# PCB_AUTO-HANDWASH-THERMOMETER.net
KiCad netlist of a schematic drawn in Altium Designer
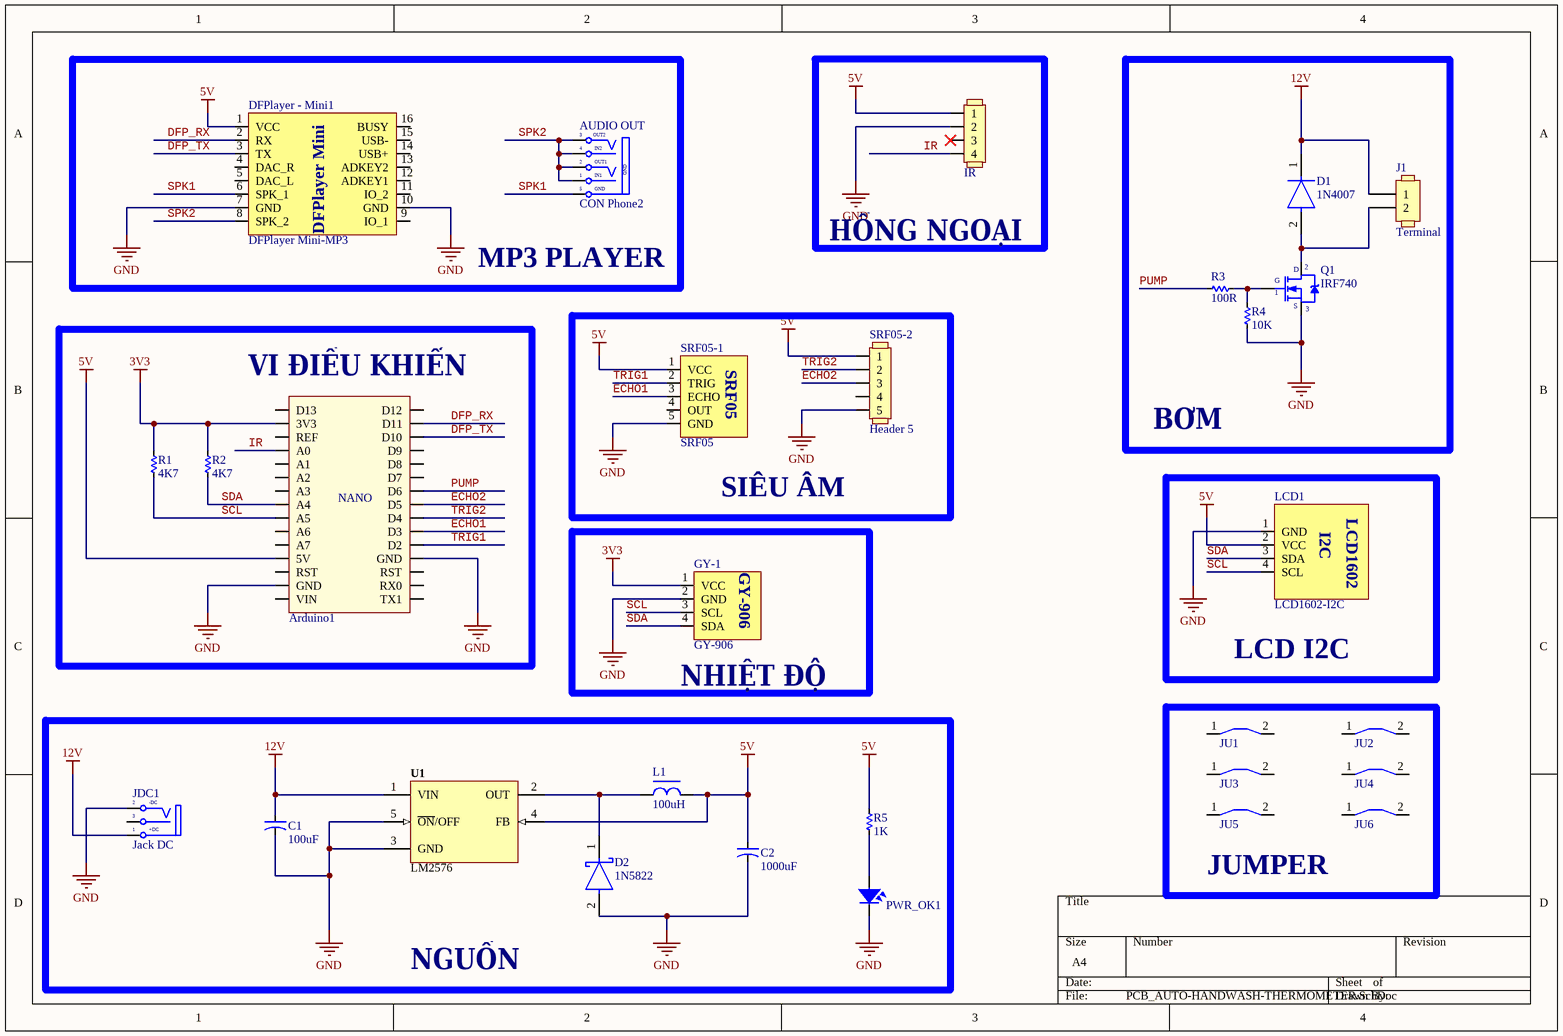
[diagram p0: PCB_AUTO-HANDWASH-THERMOMETER.SchDoc]

(export (version "E")
  (design (tool "Eeschema 10.0.6"))
  (components
    (comp (ref "Arduino1")
      (value "Arduino Nano")
      (footprint "Arduino Nano")
      (description "Arduino NANO")
      (libsource (lib "LIBRARY_MuaLinhKien") (part "Arduino Nano"))
    )
    (comp (ref "AUDIO OUT")
      (value "CON Phone2")
      (footprint "CON Phone2")
      (description "Jac Phone Stereo")
      (fields (field (name "CREAT BY") "VanDungEvn@Gmail.com"))
      (libsource (lib "LIBRARY_MuaLinhKien") (part "CON Phone2"))
    )
    (comp (ref "C1")
      (value "100uF")
      (footprint "CA-ALU-16")
      (description "Capacitor (Semiconductor SIM Model)")
      (fields (field (name "PUBLISHER") "Altium Limited"))
      (libsource (lib "LIBRARY_MuaLinhKien") (part "CN-ALU-DIP"))
    )
    (comp (ref "C2")
      (value "1000uF")
      (footprint "CA-ALU-16")
      (description "Capacitor (Semiconductor SIM Model)")
      (fields (field (name "PUBLISHER") "Altium Limited"))
      (libsource (lib "LIBRARY_MuaLinhKien") (part "CN-ALU-DIP"))
    )
    (comp (ref "D1")
      (value "1N4007")
      (footprint "FP-1N4007-MFG")
      (description "Rectifier diode 1000 V 1 A DO-41, ,")
      (fields
        (field (name "MANUFACTURER") "Diotec")
        (field (name "OCTOPART") "https://octopart.com/1n4007-diotec-4040411")
      )
      (libsource (lib "Altium Content Vault") (part "d7152d700b627762746794eb795d46e"))
    )
    (comp (ref "D2")
      (value "1N5822")
      (footprint "FP-DO-201AD-MFG")
      (description "DIODE SCHOTTKY 40V 3A DO201AD")
      (fields
        (field (name "OCTOPART") "https://octopart.com/1n5822-stmicroelectronics-323225")
        (field (name "MANUFACTURER") "STMicroelectronics")
      )
      (libsource (lib "Altium Content Vault") (part "1d6ec82d83fb6aee721767c19dac4b9"))
    )
    (comp (ref "DFPlayer - Mini1")
      (value "DFPlayer Mini-MP3")
      (footprint "DFPlayer Mini")
      (libsource (lib "tunaSchlib") (part "DFPlayer Mini-MP3"))
    )
    (comp (ref "GY-1") (value "GY-906") (footprint "GY-906") (libsource (lib "tunaSchlib") (part "GY-906")))
    (comp (ref "IR") (value "Header 4") (footprint "HEADER x4") (libsource (lib "Duc") (part "Header 4")))
    (comp (ref "J1")
      (value "Terminal")
      (footprint "Terminal x2 5mm")
      (description "Terminal x2")
      (libsource (lib "Duc") (part "Terminal x2"))
    )
    (comp (ref "JDC1")
      (value "Jack DC")
      (footprint "DC0")
      (description "Jac DC input")
      (libsource (lib "LIBRARY_MuaLinhKien") (part "DCIN"))
    )
    (comp (ref "JU1")
      (value "JUMPER")
      (footprint "JUMPER 15MM")
      (libsource (lib "tunaSchlib") (part "JUMPER"))
    )
    (comp (ref "JU2")
      (value "JUMPER")
      (footprint "JUMPER 10MM")
      (libsource (lib "tunaSchlib") (part "JUMPER"))
    )
    (comp (ref "JU3")
      (value "JUMPER")
      (footprint "JUMPER 5MM")
      (libsource (lib "tunaSchlib") (part "JUMPER"))
    )
    (comp (ref "JU4")
      (value "JUMPER")
      (footprint "JUMPER 5MM")
      (libsource (lib "tunaSchlib") (part "JUMPER"))
    )
    (comp (ref "JU5")
      (value "JUMPER")
      (footprint "JUMPER 5MM")
      (libsource (lib "tunaSchlib") (part "JUMPER"))
    )
    (comp (ref "JU6")
      (value "JUMPER")
      (footprint "JUMPER 5MM")
      (libsource (lib "tunaSchlib") (part "JUMPER"))
    )
    (comp (ref "L1")
      (value "100uH")
      (footprint "L-DIP-M-8")
      (description "Inductor")
      (libsource (lib "LIBRARY_MuaLinhKien") (part "L-DIP-1"))
    )
    (comp (ref "LCD1")
      (value "LCD1602-I2C")
      (footprint "LCD1602-I2C")
      (libsource (lib "tunaSchlib") (part "LCD1602-I2C"))
    )
    (comp (ref "PWR_OK1")
      (value "LED")
      (footprint "LED-5-RED")
      (description "LED Single colour Green and Red")
      (libsource (lib "LIBRARY_MuaLinhKien") (part "LED"))
    )
    (comp (ref "Q1")
      (value "IRF740")
      (footprint "TO220H1")
      (description "MOSFET N - CHANNEL 500V - 0.75 - 8A - TO-220")
      (libsource (lib "LIBRARY_MuaLinhKien") (part "IRF840"))
    )
    (comp (ref "R1")
      (value "4K7")
      (footprint "RES-1/4W")
      (description "Res")
      (fields
        (field (name "MANUFACTURER") "Generic Components")
        (field (name "PUBLISHER") "Altium Hobart Technology Centre")
      )
      (libsource (lib "LIBRARY_MuaLinhKien") (part "Res"))
    )
    (comp (ref "R2")
      (value "4K7")
      (footprint "RES-1/4W")
      (description "Res")
      (fields
        (field (name "MANUFACTURER") "Generic Components")
        (field (name "PUBLISHER") "Altium Hobart Technology Centre")
      )
      (libsource (lib "LIBRARY_MuaLinhKien") (part "Res"))
    )
    (comp (ref "R3")
      (value "100R")
      (footprint "RES-1/4W")
      (description "Res")
      (fields
        (field (name "MANUFACTURER") "Generic Components")
        (field (name "PUBLISHER") "Altium Hobart Technology Centre")
      )
      (libsource (lib "LIBRARY_MuaLinhKien") (part "Res"))
    )
    (comp (ref "R4")
      (value "10K")
      (footprint "RES-1/4W")
      (description "Res")
      (fields
        (field (name "MANUFACTURER") "Generic Components")
        (field (name "PUBLISHER") "Altium Hobart Technology Centre")
      )
      (libsource (lib "LIBRARY_MuaLinhKien") (part "Res"))
    )
    (comp (ref "R5")
      (value "1K")
      (footprint "RES-1/4W")
      (description "Res")
      (fields
        (field (name "MANUFACTURER") "Generic Components")
        (field (name "PUBLISHER") "Altium Hobart Technology Centre")
      )
      (libsource (lib "LIBRARY_MuaLinhKien") (part "Res"))
    )
    (comp (ref "SRF05-1") (value "SRF05") (footprint "SRF05") (libsource (lib "tunaSchlib") (part "SRF05")))
    (comp (ref "SRF05-2")
      (value "Header 5")
      (footprint "HEADER x5")
      (libsource (lib "Duc") (part "Header 5"))
    )
    (comp (ref "U1")
      (value "LM2576")
      (footprint "DIP5-T")
      (libsource (lib "LIBRARY_MuaLinhKien") (part "LM2576"))
    )
  )
  (nets
    (net (code "1") (name "/DFP_RX") (class "Default")
      (node (ref "Arduino1") (pin "D11") (pinfunction "D11_D11") (pintype "passive"))
      (node (ref "DFPlayer - Mini1") (pin "2") (pinfunction "RX_2") (pintype "power_in"))
    )
    (net (code "2") (name "/DFP_TX") (class "Default")
      (node (ref "Arduino1") (pin "D10") (pinfunction "D10_D10") (pintype "passive"))
      (node (ref "DFPlayer - Mini1") (pin "3") (pinfunction "TX_3") (pintype "power_in"))
    )
    (net (code "3") (name "/ECHO1") (class "Default")
      (node (ref "Arduino1") (pin "D3") (pinfunction "D3_D3") (pintype "passive"))
      (node (ref "SRF05-1") (pin "3") (pinfunction "ECHO_3") (pintype "power_in"))
    )
    (net (code "4") (name "/ECHO2") (class "Default")
      (node (ref "Arduino1") (pin "D5") (pinfunction "D5_D5") (pintype "passive"))
      (node (ref "SRF05-2") (pin "3") (pinfunction "3_3") (pintype "passive"))
    )
    (net (code "5") (name "/IR") (class "Default")
      (node (ref "Arduino1") (pin "A0") (pinfunction "A0_A0") (pintype "passive"))
      (node (ref "IR") (pin "4") (pinfunction "4_4") (pintype "passive"))
    )
    (net (code "6") (name "/PUMP") (class "Default")
      (node (ref "Arduino1") (pin "D6") (pinfunction "D6_D6") (pintype "passive"))
      (node (ref "R3") (pin "2") (pinfunction "2_2") (pintype "passive"))
    )
    (net (code "7") (name "/SCL") (class "Default")
      (node (ref "Arduino1") (pin "A5") (pinfunction "A5_A5") (pintype "passive"))
      (node (ref "GY-1") (pin "3") (pinfunction "SCL_3") (pintype "power_in"))
      (node (ref "LCD1") (pin "4") (pinfunction "SCL_4") (pintype "power_in"))
      (node (ref "R1") (pin "2") (pinfunction "2_2") (pintype "passive"))
    )
    (net (code "8") (name "/SDA") (class "Default")
      (node (ref "Arduino1") (pin "A4") (pinfunction "A4_A4") (pintype "passive"))
      (node (ref "GY-1") (pin "4") (pinfunction "SDA_4") (pintype "power_in"))
      (node (ref "LCD1") (pin "3") (pinfunction "SDA_3") (pintype "power_in"))
      (node (ref "R2") (pin "2") (pinfunction "2_2") (pintype "passive"))
    )
    (net (code "9") (name "/SPK1") (class "Default")
      (node (ref "AUDIO OUT") (pin "5") (pinfunction "GND_5") (pintype "passive"))
      (node (ref "DFPlayer - Mini1") (pin "6") (pinfunction "SPK_1_6") (pintype "power_in"))
    )
    (net (code "10") (name "/SPK2") (class "Default")
      (node (ref "AUDIO OUT") (pin "1") (pinfunction "S1_1") (pintype "power_in"))
      (node (ref "AUDIO OUT") (pin "2") (pinfunction "S1_2") (pintype "passive"))
      (node (ref "AUDIO OUT") (pin "3") (pinfunction "TN_3") (pintype "passive"))
      (node (ref "AUDIO OUT") (pin "4") (pinfunction "S_4") (pintype "power_in"))
      (node (ref "DFPlayer - Mini1") (pin "8") (pinfunction "SPK_2_8") (pintype "power_in"))
    )
    (net (code "11") (name "/TRIG1") (class "Default")
      (node (ref "Arduino1") (pin "D2") (pinfunction "D2_D2") (pintype "passive"))
      (node (ref "SRF05-1") (pin "2") (pinfunction "TRIG_2") (pintype "power_in"))
    )
    (net (code "12") (name "/TRIG2") (class "Default")
      (node (ref "Arduino1") (pin "D4") (pinfunction "D4_D4") (pintype "passive"))
      (node (ref "SRF05-2") (pin "2") (pinfunction "2_2") (pintype "passive"))
    )
    (net (code "13") (name "3V3") (class "Default")
      (node (ref "Arduino1") (pin "3V3") (pinfunction "3V3_3V3") (pintype "passive"))
      (node (ref "GY-1") (pin "1") (pinfunction "VCC_1") (pintype "power_in"))
      (node (ref "R1") (pin "1") (pinfunction "1_1") (pintype "passive"))
      (node (ref "R2") (pin "1") (pinfunction "1_1") (pintype "passive"))
    )
    (net (code "14") (name "5V") (class "Default")
      (node (ref "Arduino1") (pin "5V") (pinfunction "5V_5V") (pintype "passive"))
      (node (ref "C2") (pin "1") (pinfunction "1_1") (pintype "passive"))
      (node (ref "DFPlayer - Mini1") (pin "1") (pinfunction "VCC_1") (pintype "power_in"))
      (node (ref "IR") (pin "1") (pinfunction "1_1") (pintype "passive"))
      (node (ref "L1") (pin "2") (pinfunction "2_2") (pintype "passive"))
      (node (ref "LCD1") (pin "2") (pinfunction "VCC_2") (pintype "power_in"))
      (node (ref "R5") (pin "1") (pinfunction "1_1") (pintype "passive"))
      (node (ref "SRF05-1") (pin "1") (pinfunction "VCC_1") (pintype "power_in"))
      (node (ref "SRF05-2") (pin "1") (pinfunction "1_1") (pintype "passive"))
      (node (ref "U1") (pin "4") (pinfunction "FB_4") (pintype "input"))
    )
    (net (code "15") (name "12V") (class "Default")
      (node (ref "C1") (pin "1") (pinfunction "1_1") (pintype "passive"))
      (node (ref "D1") (pin "1") (pinfunction "C_1") (pintype "passive"))
      (node (ref "J1") (pin "1") (pinfunction "1_1") (pintype "passive"))
      (node (ref "JDC1") (pin "1") (pinfunction "T_1") (pintype "passive"))
      (node (ref "U1") (pin "1") (pinfunction "VIN_1") (pintype "power_in"))
    )
    (net (code "16") (name "GND") (class "Default")
      (node (ref "Arduino1") (pin "GND") (pinfunction "GND_GND") (pintype "passive"))
      (node (ref "C1") (pin "2") (pinfunction "2_2") (pintype "passive"))
      (node (ref "C2") (pin "2") (pinfunction "2_2") (pintype "passive"))
      (node (ref "D2") (pin "2") (pinfunction "A_2") (pintype "passive"))
      (node (ref "DFPlayer - Mini1") (pin "10") (pinfunction "GND_10") (pintype "power_in"))
      (node (ref "DFPlayer - Mini1") (pin "7") (pinfunction "GND_7") (pintype "power_in"))
      (node (ref "GY-1") (pin "2") (pinfunction "GND_2") (pintype "power_in"))
      (node (ref "IR") (pin "2") (pinfunction "2_2") (pintype "passive"))
      (node (ref "JDC1") (pin "2") (pinfunction "TN_2") (pintype "passive"))
      (node (ref "LCD1") (pin "1") (pinfunction "GND_1") (pintype "power_in"))
      (node (ref "PWR_OK1") (pin "2") (pinfunction "2_2") (pintype "passive"))
      (node (ref "Q1") (pin "3") (pinfunction "S_3") (pintype "passive"))
      (node (ref "R4") (pin "2") (pinfunction "2_2") (pintype "passive"))
      (node (ref "SRF05-1") (pin "5") (pinfunction "GND_5") (pintype "power_in"))
      (node (ref "SRF05-2") (pin "5") (pinfunction "5_5") (pintype "passive"))
      (node (ref "U1") (pin "3") (pinfunction "GND_3") (pintype "power_in"))
      (node (ref "U1") (pin "5") (pinfunction "~{ON}/OFF_5") (pintype "input"))
    )
    (net (code "17") (name "Net-(D1-A)") (class "Default")
      (node (ref "D1") (pin "2") (pinfunction "A_2") (pintype "passive"))
      (node (ref "J1") (pin "2") (pinfunction "2_2") (pintype "passive"))
      (node (ref "Q1") (pin "2") (pinfunction "D_2") (pintype "passive"))
    )
    (net (code "18") (name "Net-(D2-C)") (class "Default")
      (node (ref "D2") (pin "1") (pinfunction "C_1") (pintype "passive"))
      (node (ref "L1") (pin "1") (pinfunction "1_1") (pintype "passive"))
      (node (ref "U1") (pin "2") (pinfunction "OUT_2") (pintype "power_in"))
    )
    (net (code "19") (name "Net-(PWR_OK1-Pad1)") (class "Default")
      (node (ref "PWR_OK1") (pin "1") (pinfunction "1_1") (pintype "passive"))
      (node (ref "R5") (pin "2") (pinfunction "2_2") (pintype "passive"))
    )
    (net (code "20") (name "Net-(Q1-G)") (class "Default")
      (node (ref "Q1") (pin "1") (pinfunction "G_1") (pintype "passive"))
      (node (ref "R3") (pin "1") (pinfunction "1_1") (pintype "passive"))
      (node (ref "R4") (pin "1") (pinfunction "1_1") (pintype "passive"))
    )
    (net (code "21") (name "unconnected-(Arduino1-PadA1)") (class "Default")
      (node (ref "Arduino1") (pin "A1") (pinfunction "A1_A1") (pintype "passive"))
    )
    (net (code "22") (name "unconnected-(Arduino1-PadA2)") (class "Default")
      (node (ref "Arduino1") (pin "A2") (pinfunction "A2_A2") (pintype "passive"))
    )
    (net (code "23") (name "unconnected-(Arduino1-PadA3)") (class "Default")
      (node (ref "Arduino1") (pin "A3") (pinfunction "A3_A3") (pintype "passive"))
    )
    (net (code "24") (name "unconnected-(Arduino1-PadA6)") (class "Default")
      (node (ref "Arduino1") (pin "A6") (pinfunction "A6_A6") (pintype "passive"))
    )
    (net (code "25") (name "unconnected-(Arduino1-PadA7)") (class "Default")
      (node (ref "Arduino1") (pin "A7") (pinfunction "A7_A7") (pintype "passive"))
    )
    (net (code "26") (name "unconnected-(Arduino1-PadD7)") (class "Default")
      (node (ref "Arduino1") (pin "D7") (pinfunction "D7_D7") (pintype "passive"))
    )
    (net (code "27") (name "unconnected-(Arduino1-PadD8)") (class "Default")
      (node (ref "Arduino1") (pin "D8") (pinfunction "D8_D8") (pintype "passive"))
    )
    (net (code "28") (name "unconnected-(Arduino1-PadD9)") (class "Default")
      (node (ref "Arduino1") (pin "D9") (pinfunction "D9_D9") (pintype "passive"))
    )
    (net (code "29") (name "unconnected-(Arduino1-PadD12)") (class "Default")
      (node (ref "Arduino1") (pin "D12") (pinfunction "D12_D12") (pintype "passive"))
    )
    (net (code "30") (name "unconnected-(Arduino1-PadD13)") (class "Default")
      (node (ref "Arduino1") (pin "D13") (pinfunction "D13_D13") (pintype "passive"))
    )
    (net (code "31") (name "unconnected-(Arduino1-PadREF)") (class "Default")
      (node (ref "Arduino1") (pin "REF") (pinfunction "REF_REF") (pintype "passive"))
    )
    (net (code "32") (name "unconnected-(Arduino1-PadRST)") (class "Default")
      (node (ref "Arduino1") (pin "RST") (pinfunction "RST_RST") (pintype "passive"))
    )
    (net (code "33") (name "unconnected-(Arduino1-PadRST)_1") (class "Default")
      (node (ref "Arduino1") (pin "RST") (pinfunction "RST_RST") (pintype "passive"))
    )
    (net (code "34") (name "unconnected-(Arduino1-PadRX0)") (class "Default")
      (node (ref "Arduino1") (pin "RX0") (pinfunction "RX0_RX0") (pintype "passive"))
    )
    (net (code "35") (name "unconnected-(Arduino1-PadTX1)") (class "Default")
      (node (ref "Arduino1") (pin "TX1") (pinfunction "TX1_TX1") (pintype "passive"))
    )
    (net (code "36") (name "unconnected-(Arduino1-PadVIN)") (class "Default")
      (node (ref "Arduino1") (pin "VIN") (pinfunction "VIN_VIN") (pintype "passive"))
    )
    (net (code "37") (name "unconnected-(DFPlayer - Mini1-ADKEY1-Pad12)") (class "Default")
      (node (ref "DFPlayer - Mini1") (pin "12") (pinfunction "ADKEY1_12") (pintype "power_in"))
    )
    (net (code "38") (name "unconnected-(DFPlayer - Mini1-ADKEY2-Pad13)") (class "Default")
      (node (ref "DFPlayer - Mini1") (pin "13") (pinfunction "ADKEY2_13") (pintype "power_in"))
    )
    (net (code "39") (name "unconnected-(DFPlayer - Mini1-BUSY-Pad16)") (class "Default")
      (node (ref "DFPlayer - Mini1") (pin "16") (pinfunction "BUSY_16") (pintype "power_in"))
    )
    (net (code "40") (name "unconnected-(DFPlayer - Mini1-DAC_L-Pad5)") (class "Default")
      (node (ref "DFPlayer - Mini1") (pin "5") (pinfunction "DAC_L_5") (pintype "power_in"))
    )
    (net (code "41") (name "unconnected-(DFPlayer - Mini1-DAC_R-Pad4)") (class "Default")
      (node (ref "DFPlayer - Mini1") (pin "4") (pinfunction "DAC_R_4") (pintype "power_in"))
    )
    (net (code "42") (name "unconnected-(DFPlayer - Mini1-IO_1-Pad9)") (class "Default")
      (node (ref "DFPlayer - Mini1") (pin "9") (pinfunction "IO_1_9") (pintype "power_in"))
    )
    (net (code "43") (name "unconnected-(DFPlayer - Mini1-IO_2-Pad11)") (class "Default")
      (node (ref "DFPlayer - Mini1") (pin "11") (pinfunction "IO_2_11") (pintype "power_in"))
    )
    (net (code "44") (name "unconnected-(DFPlayer - Mini1-USB+-Pad14)") (class "Default")
      (node (ref "DFPlayer - Mini1") (pin "14") (pinfunction "USB+_14") (pintype "power_in"))
    )
    (net (code "45") (name "unconnected-(DFPlayer - Mini1-USB--Pad15)") (class "Default")
      (node (ref "DFPlayer - Mini1") (pin "15") (pinfunction "USB-_15") (pintype "power_in"))
    )
    (net (code "46") (name "unconnected-(IR-Pad3)") (class "Default")
      (node (ref "IR") (pin "3") (pinfunction "3_3") (pintype "passive+no_connect"))
    )
    (net (code "47") (name "unconnected-(JDC1-S-Pad3)") (class "Default")
      (node (ref "JDC1") (pin "3") (pinfunction "S_3") (pintype "power_in"))
    )
    (net (code "48") (name "unconnected-(JU1-Pad1)") (class "Default")
      (node (ref "JU1") (pin "1") (pinfunction "1_1") (pintype "power_in"))
    )
    (net (code "49") (name "unconnected-(JU1-Pad2)") (class "Default")
      (node (ref "JU1") (pin "2") (pinfunction "2_2") (pintype "power_in"))
    )
    (net (code "50") (name "unconnected-(JU2-Pad1)") (class "Default")
      (node (ref "JU2") (pin "1") (pinfunction "1_1") (pintype "power_in"))
    )
    (net (code "51") (name "unconnected-(JU2-Pad2)") (class "Default")
      (node (ref "JU2") (pin "2") (pinfunction "2_2") (pintype "power_in"))
    )
    (net (code "52") (name "unconnected-(JU3-Pad1)") (class "Default")
      (node (ref "JU3") (pin "1") (pinfunction "1_1") (pintype "power_in"))
    )
    (net (code "53") (name "unconnected-(JU3-Pad2)") (class "Default")
      (node (ref "JU3") (pin "2") (pinfunction "2_2") (pintype "power_in"))
    )
    (net (code "54") (name "unconnected-(JU4-Pad1)") (class "Default")
      (node (ref "JU4") (pin "1") (pinfunction "1_1") (pintype "power_in"))
    )
    (net (code "55") (name "unconnected-(JU4-Pad2)") (class "Default")
      (node (ref "JU4") (pin "2") (pinfunction "2_2") (pintype "power_in"))
    )
    (net (code "56") (name "unconnected-(JU5-Pad1)") (class "Default")
      (node (ref "JU5") (pin "1") (pinfunction "1_1") (pintype "power_in"))
    )
    (net (code "57") (name "unconnected-(JU5-Pad2)") (class "Default")
      (node (ref "JU5") (pin "2") (pinfunction "2_2") (pintype "power_in"))
    )
    (net (code "58") (name "unconnected-(JU6-Pad1)") (class "Default")
      (node (ref "JU6") (pin "1") (pinfunction "1_1") (pintype "power_in"))
    )
    (net (code "59") (name "unconnected-(JU6-Pad2)") (class "Default")
      (node (ref "JU6") (pin "2") (pinfunction "2_2") (pintype "power_in"))
    )
    (net (code "60") (name "unconnected-(SRF05-1-OUT-Pad4)") (class "Default")
      (node (ref "SRF05-1") (pin "4") (pinfunction "OUT_4") (pintype "power_in"))
    )
    (net (code "61") (name "unconnected-(SRF05-2-Pad4)") (class "Default")
      (node (ref "SRF05-2") (pin "4") (pinfunction "4_4") (pintype "passive"))
    )
  )
)
